# 3-RF_Frontend.net
KiCad netlist of a schematic drawn in Altium Designer
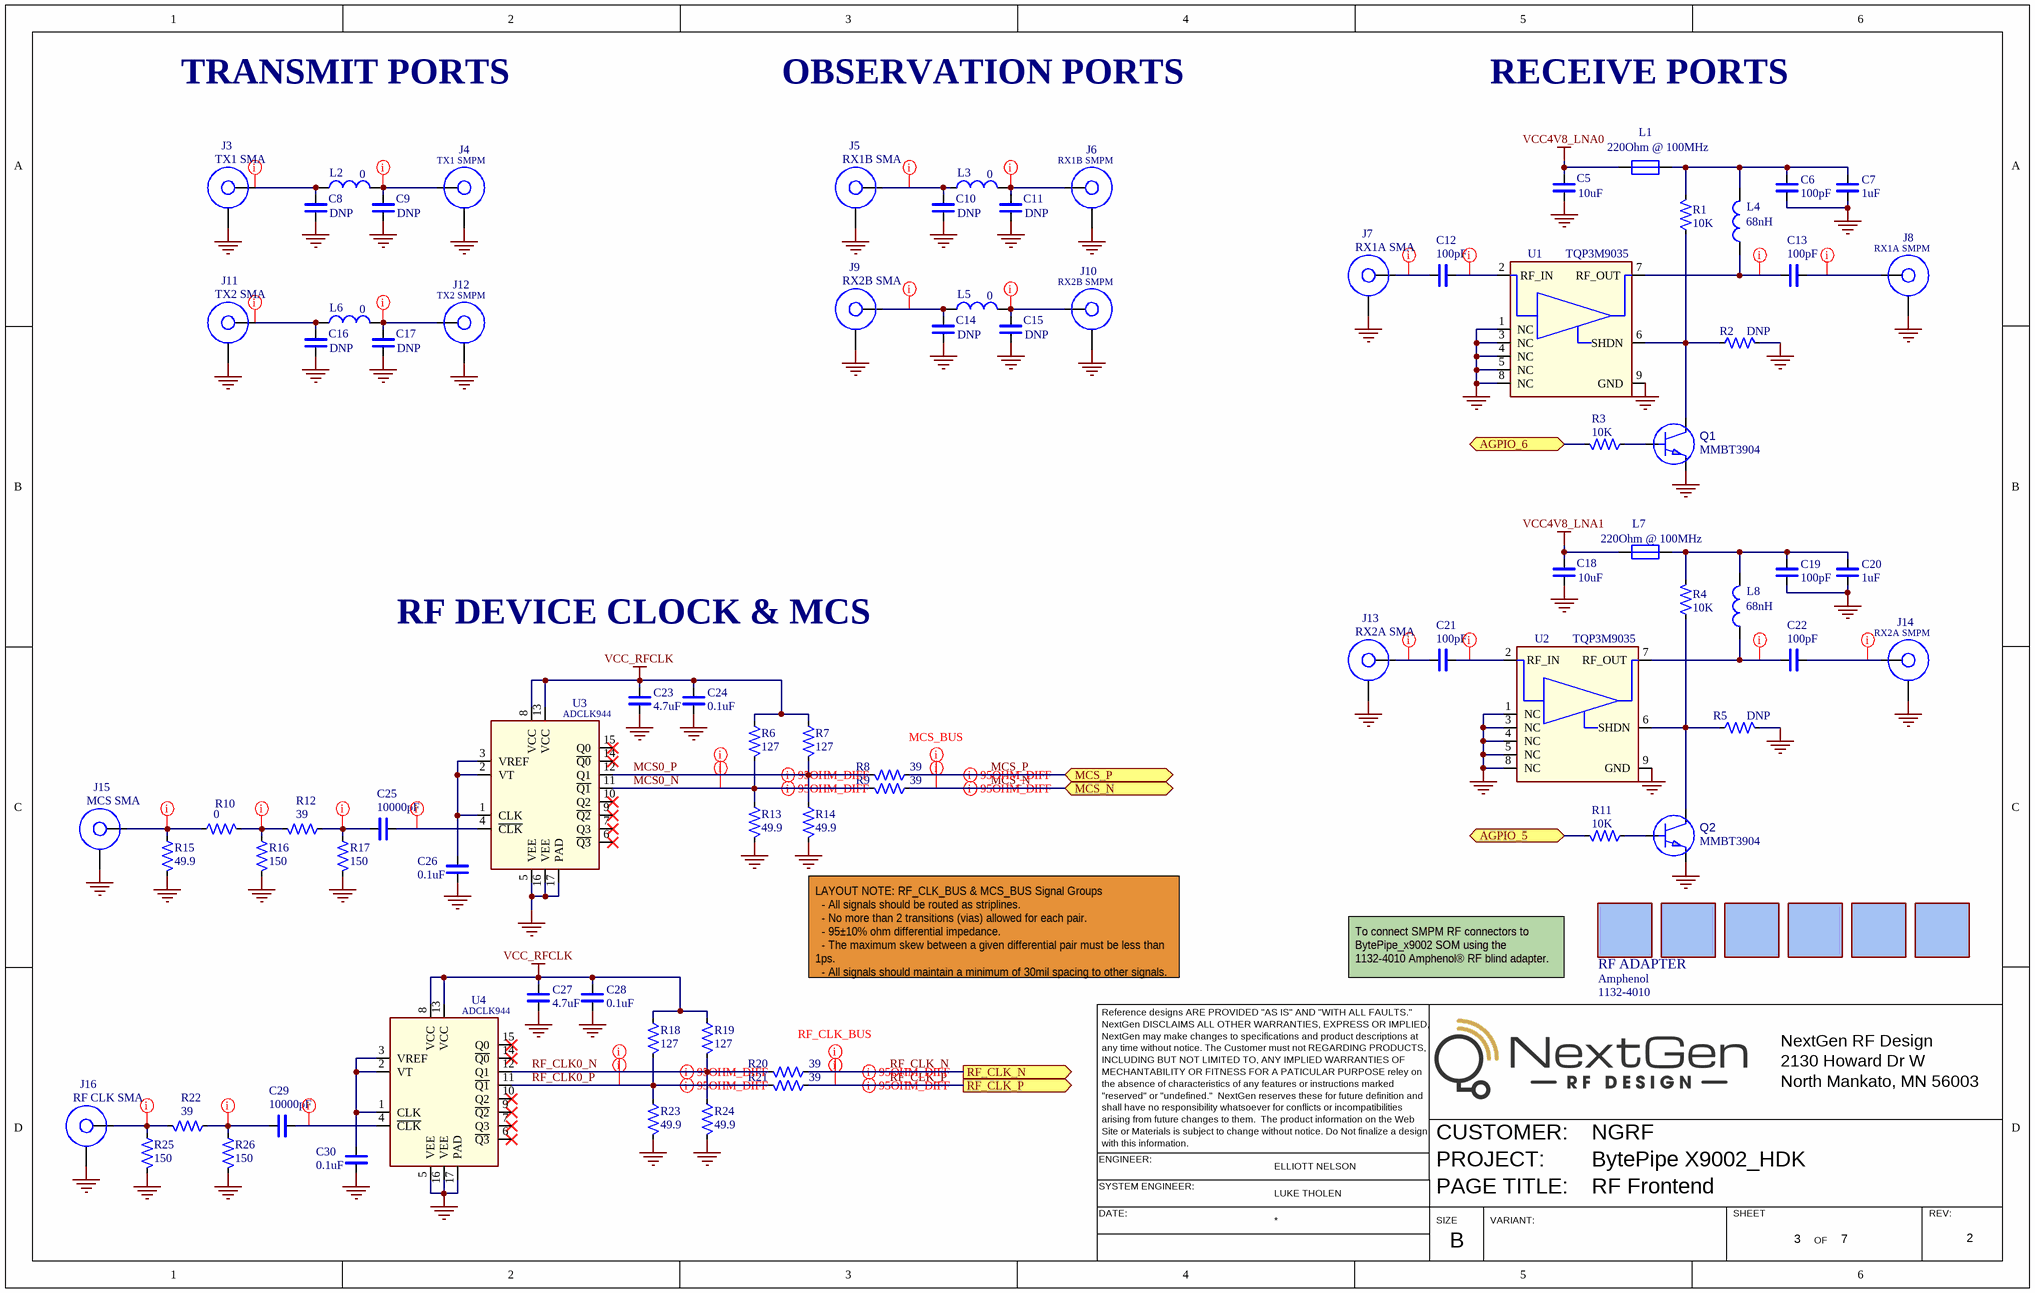
[diagram p0: 3-RF Frontend.SchDoc]

(export (version "E")
  (design (tool "Eeschema 10.0.6"))
  (components
    (comp (ref "B3")
      (value "RF ADAPTER")
      (description "Amphenol® RF SMPM blind adapter")
      (fields (field (name "OEM NAME") "Amphenol") (field (name "OEM#") "1132-4010"))
      (libsource (lib "NextGenRF_Symbols_MECH") (part "BOM_COMPONENT_NO-FOOTPRINT"))
    )
    (comp (ref "B4")
      (value "RF ADAPTER")
      (description "Amphenol® RF SMPM blind adapter")
      (libsource (lib "NextGenRF_Symbols_MECH") (part "BOM_COMPONENT_NO-FOOTPRINT"))
    )
    (comp (ref "B5")
      (value "RF ADAPTER")
      (description "Amphenol® RF SMPM blind adapter")
      (libsource (lib "NextGenRF_Symbols_MECH") (part "BOM_COMPONENT_NO-FOOTPRINT"))
    )
    (comp (ref "B6")
      (value "RF ADAPTER")
      (description "Amphenol® RF SMPM blind adapter")
      (libsource (lib "NextGenRF_Symbols_MECH") (part "BOM_COMPONENT_NO-FOOTPRINT"))
    )
    (comp (ref "B7")
      (value "RF ADAPTER")
      (description "Amphenol® RF SMPM blind adapter")
      (libsource (lib "NextGenRF_Symbols_MECH") (part "BOM_COMPONENT_NO-FOOTPRINT"))
    )
    (comp (ref "B8")
      (value "RF ADAPTER")
      (description "Amphenol® RF SMPM blind adapter")
      (libsource (lib "NextGenRF_Symbols_MECH") (part "BOM_COMPONENT_NO-FOOTPRINT"))
    )
    (comp (ref "C5")
      (value "10uF")
      (footprint "SM/0402/CAP")
      (description "10µF ±20% 10V Ceramic Capacitor X5R 0402 (1005 Metric)")
      (fields (field (name "Comment") "CAP_CERAMIC_0402"))
      (libsource (lib "NextGenRF_Symbols_SMT") (part "CAP_CERAMIC_0402"))
    )
    (comp (ref "C6")
      (value "100pF")
      (footprint "SM/0402/CAP")
      (description "CAP CER 100PF 50V C0G/NP0 0402")
      (fields (field (name "Comment") "CAP_CERAMIC_0402"))
      (libsource (lib "NextGenRF_Symbols_SMT") (part "CAP_CERAMIC_0402"))
    )
    (comp (ref "C7")
      (value "1uF")
      (footprint "SM/0402/CAP")
      (description "CAP CER 1UF 16V X5R 0402")
      (fields (field (name "Comment") "CAP_CERAMIC_0402"))
      (libsource (lib "NextGenRF_Symbols_SMT") (part "CAP_CERAMIC_0402"))
    )
    (comp (ref "C8")
      (value "DNP")
      (footprint "SM/0402/CAP")
      (fields (field (name "Comment") "CAP_CERAMIC_0402"))
      (libsource (lib "NextGenRF_Symbols_SMT") (part "CAP_CERAMIC_0402"))
    )
    (comp (ref "C9")
      (value "DNP")
      (footprint "SM/0402/CAP")
      (fields (field (name "Comment") "CAP_CERAMIC_0402"))
      (libsource (lib "NextGenRF_Symbols_SMT") (part "CAP_CERAMIC_0402"))
    )
    (comp (ref "C10")
      (value "DNP")
      (footprint "SM/0402/CAP")
      (fields (field (name "Comment") "CAP_CERAMIC_0402"))
      (libsource (lib "NextGenRF_Symbols_SMT") (part "CAP_CERAMIC_0402"))
    )
    (comp (ref "C11")
      (value "DNP")
      (footprint "SM/0402/CAP")
      (fields (field (name "Comment") "CAP_CERAMIC_0402"))
      (libsource (lib "NextGenRF_Symbols_SMT") (part "CAP_CERAMIC_0402"))
    )
    (comp (ref "C12")
      (value "100pF")
      (footprint "SM/0402/CAP")
      (description "CAP CER 100PF 50V C0G/NP0 0402")
      (fields (field (name "Comment") "CAP_CERAMIC_0402"))
      (libsource (lib "NextGenRF_Symbols_SMT") (part "CAP_CERAMIC_0402"))
    )
    (comp (ref "C13")
      (value "100pF")
      (footprint "SM/0402/CAP")
      (description "CAP CER 100PF 50V C0G/NP0 0402")
      (fields (field (name "Comment") "CAP_CERAMIC_0402"))
      (libsource (lib "NextGenRF_Symbols_SMT") (part "CAP_CERAMIC_0402"))
    )
    (comp (ref "C14")
      (value "DNP")
      (footprint "SM/0402/CAP")
      (fields (field (name "Comment") "CAP_CERAMIC_0402"))
      (libsource (lib "NextGenRF_Symbols_SMT") (part "CAP_CERAMIC_0402"))
    )
    (comp (ref "C15")
      (value "DNP")
      (footprint "SM/0402/CAP")
      (fields (field (name "Comment") "CAP_CERAMIC_0402"))
      (libsource (lib "NextGenRF_Symbols_SMT") (part "CAP_CERAMIC_0402"))
    )
    (comp (ref "C16")
      (value "DNP")
      (footprint "SM/0402/CAP")
      (fields (field (name "Comment") "CAP_CERAMIC_0402"))
      (libsource (lib "NextGenRF_Symbols_SMT") (part "CAP_CERAMIC_0402"))
    )
    (comp (ref "C17")
      (value "DNP")
      (footprint "SM/0402/CAP")
      (fields (field (name "Comment") "CAP_CERAMIC_0402"))
      (libsource (lib "NextGenRF_Symbols_SMT") (part "CAP_CERAMIC_0402"))
    )
    (comp (ref "C18")
      (value "10uF")
      (footprint "SM/0402/CAP")
      (description "10µF ±20% 10V Ceramic Capacitor X5R 0402 (1005 Metric)")
      (fields (field (name "Comment") "CAP_CERAMIC_0402"))
      (libsource (lib "NextGenRF_Symbols_SMT") (part "CAP_CERAMIC_0402"))
    )
    (comp (ref "C19")
      (value "100pF")
      (footprint "SM/0402/CAP")
      (description "CAP CER 100PF 50V C0G/NP0 0402")
      (fields (field (name "Comment") "CAP_CERAMIC_0402"))
      (libsource (lib "NextGenRF_Symbols_SMT") (part "CAP_CERAMIC_0402"))
    )
    (comp (ref "C20")
      (value "1uF")
      (footprint "SM/0402/CAP")
      (description "CAP CER 1UF 16V X5R 0402")
      (fields (field (name "Comment") "CAP_CERAMIC_0402"))
      (libsource (lib "NextGenRF_Symbols_SMT") (part "CAP_CERAMIC_0402"))
    )
    (comp (ref "C21")
      (value "100pF")
      (footprint "SM/0402/CAP")
      (description "CAP CER 100PF 50V C0G/NP0 0402")
      (fields (field (name "Comment") "CAP_CERAMIC_0402"))
      (libsource (lib "NextGenRF_Symbols_SMT") (part "CAP_CERAMIC_0402"))
    )
    (comp (ref "C22")
      (value "100pF")
      (footprint "SM/0402/CAP")
      (description "CAP CER 100PF 50V C0G/NP0 0402")
      (fields (field (name "Comment") "CAP_CERAMIC_0402"))
      (libsource (lib "NextGenRF_Symbols_SMT") (part "CAP_CERAMIC_0402"))
    )
    (comp (ref "C23")
      (value "4.7uF")
      (footprint "SM/0402/CAP")
      (description "CAP CER 4.7UF 10V X5R 0402")
      (fields (field (name "Comment") "CAP_CERAMIC_0402"))
      (libsource (lib "NextGenRF_Symbols_SMT") (part "CAP_CERAMIC_0402"))
    )
    (comp (ref "C24")
      (value "0.1uF")
      (footprint "SM/0402/CAP")
      (description "CAP CER 0.1UF 25V X7R 0402")
      (fields (field (name "Comment") "CAP_CERAMIC_0402"))
      (libsource (lib "NextGenRF_Symbols_SMT") (part "CAP_CERAMIC_0402"))
    )
    (comp (ref "C25")
      (value "10000pF")
      (footprint "SM/0402/CAP")
      (description "CAP CER 10000PF 50V X7R 0402")
      (fields (field (name "Comment") "CAP_CERAMIC_0402"))
      (libsource (lib "NextGenRF_Symbols_SMT") (part "CAP_CERAMIC_0402"))
    )
    (comp (ref "C26")
      (value "0.1uF")
      (footprint "SM/0402/CAP")
      (description "CAP CER 0.1UF 25V X7R 0402")
      (fields (field (name "Comment") "CAP_CERAMIC_0402"))
      (libsource (lib "NextGenRF_Symbols_SMT") (part "CAP_CERAMIC_0402"))
    )
    (comp (ref "C27")
      (value "4.7uF")
      (footprint "SM/0402/CAP")
      (description "CAP CER 4.7UF 10V X5R 0402")
      (fields (field (name "Comment") "CAP_CERAMIC_0402"))
      (libsource (lib "NextGenRF_Symbols_SMT") (part "CAP_CERAMIC_0402"))
    )
    (comp (ref "C28")
      (value "0.1uF")
      (footprint "SM/0402/CAP")
      (description "CAP CER 0.1UF 25V X7R 0402")
      (fields (field (name "Comment") "CAP_CERAMIC_0402"))
      (libsource (lib "NextGenRF_Symbols_SMT") (part "CAP_CERAMIC_0402"))
    )
    (comp (ref "C29")
      (value "10000pF")
      (footprint "SM/0402/CAP")
      (description "CAP CER 10000PF 50V X7R 0402")
      (fields (field (name "Comment") "CAP_CERAMIC_0402"))
      (libsource (lib "NextGenRF_Symbols_SMT") (part "CAP_CERAMIC_0402"))
    )
    (comp (ref "C30")
      (value "0.1uF")
      (footprint "SM/0402/CAP")
      (description "CAP CER 0.1UF 25V X7R 0402")
      (fields (field (name "Comment") "CAP_CERAMIC_0402"))
      (libsource (lib "NextGenRF_Symbols_SMT") (part "CAP_CERAMIC_0402"))
    )
    (comp (ref "J3")
      (value "TX1 SMA")
      (footprint "NGRF_SMT_Footprints:SM/CON/RF/SMA/BRD-EDGE_C")
      (description "SMA board edge style, .250\" wide style")
      (fields (field (name "Comment") "CON_RF_SMA_BRD-EDGE_C"))
      (libsource (lib "NextGenRF_Symbols_SMT") (part "CON_RF_SMA_BRD-EDGE_C"))
    )
    (comp (ref "J4")
      (value "TX1 SMPM")
      (footprint "SM/CON/RF/SMPM/VERT_A")
      (description "SMPM Connector Plug, Male Pin 50Ohm Surface Mount Solder. Based off of Amphenol 925-144J-51PT")
      (fields (field (name "Comment") "CON_RF_SMPM_SMT_AMPHENOL"))
      (libsource (lib "NextGenRF_Symbols_SMT") (part "CON_RF_SMPM_SMT_AMPHENOL"))
    )
    (comp (ref "J5")
      (value "RX1B SMA")
      (footprint "NGRF_SMT_Footprints:SM/CON/RF/SMA/BRD-EDGE_C")
      (description "SMA board edge style, .250\" wide style")
      (fields (field (name "Comment") "CON_RF_SMA_BRD-EDGE_C"))
      (libsource (lib "NextGenRF_Symbols_SMT") (part "CON_RF_SMA_BRD-EDGE_C"))
    )
    (comp (ref "J6")
      (value "RX1B SMPM")
      (footprint "SM/CON/RF/SMPM/VERT_A")
      (description "SMPM Connector Plug, Male Pin 50Ohm Surface Mount Solder. Based off of Amphenol 925-144J-51PT")
      (fields (field (name "Comment") "CON_RF_SMPM_SMT_AMPHENOL"))
      (libsource (lib "NextGenRF_Symbols_SMT") (part "CON_RF_SMPM_SMT_AMPHENOL"))
    )
    (comp (ref "J7")
      (value "RX1A SMA")
      (footprint "NGRF_SMT_Footprints:SM/CON/RF/SMA/BRD-EDGE_C")
      (description "SMA board edge style, .250\" wide style")
      (fields (field (name "Comment") "CON_RF_SMA_BRD-EDGE_C"))
      (libsource (lib "NextGenRF_Symbols_SMT") (part "CON_RF_SMA_BRD-EDGE_C"))
    )
    (comp (ref "J8")
      (value "RX1A SMPM")
      (footprint "SM/CON/RF/SMPM/VERT_A")
      (description "SMPM Connector Plug, Male Pin 50Ohm Surface Mount Solder. Based off of Amphenol 925-144J-51PT")
      (fields (field (name "Comment") "CON_RF_SMPM_SMT_AMPHENOL"))
      (libsource (lib "NextGenRF_Symbols_SMT") (part "CON_RF_SMPM_SMT_AMPHENOL"))
    )
    (comp (ref "J9")
      (value "RX2B SMA")
      (footprint "NGRF_SMT_Footprints:SM/CON/RF/SMA/BRD-EDGE_C")
      (description "SMA board edge style, .250\" wide style")
      (fields (field (name "Comment") "CON_RF_SMA_BRD-EDGE_C"))
      (libsource (lib "NextGenRF_Symbols_SMT") (part "CON_RF_SMA_BRD-EDGE_C"))
    )
    (comp (ref "J10")
      (value "RX2B SMPM")
      (footprint "SM/CON/RF/SMPM/VERT_A")
      (description "SMPM Connector Plug, Male Pin 50Ohm Surface Mount Solder. Based off of Amphenol 925-144J-51PT")
      (fields (field (name "Comment") "CON_RF_SMPM_SMT_AMPHENOL"))
      (libsource (lib "NextGenRF_Symbols_SMT") (part "CON_RF_SMPM_SMT_AMPHENOL"))
    )
    (comp (ref "J11")
      (value "TX2 SMA")
      (footprint "NGRF_SMT_Footprints:SM/CON/RF/SMA/BRD-EDGE_C")
      (description "SMA board edge style, .250\" wide style")
      (fields (field (name "Comment") "CON_RF_SMA_BRD-EDGE_C"))
      (libsource (lib "NextGenRF_Symbols_SMT") (part "CON_RF_SMA_BRD-EDGE_C"))
    )
    (comp (ref "J12")
      (value "TX2 SMPM")
      (footprint "SM/CON/RF/SMPM/VERT_A")
      (description "SMPM Connector Plug, Male Pin 50Ohm Surface Mount Solder. Based off of Amphenol 925-144J-51PT")
      (fields (field (name "Comment") "CON_RF_SMPM_SMT_AMPHENOL"))
      (libsource (lib "NextGenRF_Symbols_SMT") (part "CON_RF_SMPM_SMT_AMPHENOL"))
    )
    (comp (ref "J13")
      (value "RX2A SMA")
      (footprint "NGRF_SMT_Footprints:SM/CON/RF/SMA/BRD-EDGE_C")
      (description "SMA board edge style, .250\" wide style")
      (fields (field (name "Comment") "CON_RF_SMA_BRD-EDGE_C"))
      (libsource (lib "NextGenRF_Symbols_SMT") (part "CON_RF_SMA_BRD-EDGE_C"))
    )
    (comp (ref "J14")
      (value "RX2A SMPM")
      (footprint "SM/CON/RF/SMPM/VERT_A")
      (description "SMPM Connector Plug, Male Pin 50Ohm Surface Mount Solder. Based off of Amphenol 925-144J-51PT")
      (fields (field (name "Comment") "CON_RF_SMPM_SMT_AMPHENOL"))
      (libsource (lib "NextGenRF_Symbols_SMT") (part "CON_RF_SMPM_SMT_AMPHENOL"))
    )
    (comp (ref "J15")
      (value "MCS SMA")
      (footprint "NGRF_SMT_Footprints:SM/CON/RF/SMA/BRD-EDGE_C")
      (description "SMA board edge style, .250\" wide style")
      (fields (field (name "Comment") "CON_RF_SMA_BRD-EDGE_C"))
      (libsource (lib "NextGenRF_Symbols_SMT") (part "CON_RF_SMA_BRD-EDGE_C"))
    )
    (comp (ref "J16")
      (value "RF CLK SMA")
      (footprint "NGRF_SMT_Footprints:SM/CON/RF/SMA/BRD-EDGE_C")
      (description "SMA board edge style, .250\" wide style")
      (fields (field (name "Comment") "CON_RF_SMA_BRD-EDGE_C"))
      (libsource (lib "NextGenRF_Symbols_SMT") (part "CON_RF_SMA_BRD-EDGE_C"))
    )
    (comp (ref "L1")
      (value "220Ohm @ 100MHz")
      (footprint "NGRF_SMT_Footprints:SM/0603")
      (description "120 Ohms @ 100MHz 1 Power Line Ferrite Bead 0603 (1608 Metric) 3A 25mOhm")
      (fields (field (name "Comment") "FERRITE_0603_A"))
      (libsource (lib "NextGenRF_Symbols_SMT") (part "FERRITE_0603_A"))
    )
    (comp (ref "L2")
      (value "0")
      (footprint "NGRF_SMT_Footprints:SM/0402")
      (description "RES SMD 0 OHM JUMPER 1/10W 0402")
      (fields (field (name "Comment") "IND_0402"))
      (libsource (lib "NextGenRF_Symbols_SMT") (part "IND_0402"))
    )
    (comp (ref "L3")
      (value "0")
      (footprint "NGRF_SMT_Footprints:SM/0402")
      (description "RES SMD 0 OHM JUMPER 1/10W 0402")
      (fields (field (name "Comment") "IND_0402"))
      (libsource (lib "NextGenRF_Symbols_SMT") (part "IND_0402"))
    )
    (comp (ref "L4")
      (value "68nH")
      (footprint "NGRF_SMT_Footprints:SM/0603")
      (description "FIXED IND 68NH 300MA 800 MOHM")
      (fields (field (name "Comment") "IND_0603"))
      (libsource (lib "NextGenRF_Symbols_SMT") (part "IND_0603"))
    )
    (comp (ref "L5")
      (value "0")
      (footprint "NGRF_SMT_Footprints:SM/0402")
      (description "RES SMD 0 OHM JUMPER 1/10W 0402")
      (fields (field (name "Comment") "IND_0402"))
      (libsource (lib "NextGenRF_Symbols_SMT") (part "IND_0402"))
    )
    (comp (ref "L6")
      (value "0")
      (footprint "NGRF_SMT_Footprints:SM/0402")
      (description "RES SMD 0 OHM JUMPER 1/10W 0402")
      (fields (field (name "Comment") "IND_0402"))
      (libsource (lib "NextGenRF_Symbols_SMT") (part "IND_0402"))
    )
    (comp (ref "L7")
      (value "220Ohm @ 100MHz")
      (footprint "NGRF_SMT_Footprints:SM/0603")
      (description "120 Ohms @ 100MHz 1 Power Line Ferrite Bead 0603 (1608 Metric) 3A 25mOhm")
      (fields (field (name "Comment") "FERRITE_0603_A"))
      (libsource (lib "NextGenRF_Symbols_SMT") (part "FERRITE_0603_A"))
    )
    (comp (ref "L8")
      (value "68nH")
      (footprint "NGRF_SMT_Footprints:SM/0603")
      (description "FIXED IND 68NH 300MA 800 MOHM")
      (fields (field (name "Comment") "IND_0603"))
      (libsource (lib "NextGenRF_Symbols_SMT") (part "IND_0603"))
    )
    (comp (ref "Q1")
      (value "MMBT3904")
      (footprint "NGRF_SMT_Footprints:SM/SOT23_A")
      (description "Bipolar (BJT) Transistor NPN 40V 200mA 300MHz 300mW Surface Mount SOT-23-3 (TO-236)")
      (fields (field (name "Comment") "TRANSISTOR_NPN_SOT23"))
      (libsource (lib "NextGenRF_Symbols_SMT") (part "TRANSISTOR_NPN_SOT23"))
    )
    (comp (ref "Q2")
      (value "MMBT3904")
      (footprint "NGRF_SMT_Footprints:SM/SOT23_A")
      (description "Bipolar (BJT) Transistor NPN 40V 200mA 300MHz 300mW Surface Mount SOT-23-3 (TO-236)")
      (fields (field (name "Comment") "TRANSISTOR_NPN_SOT23"))
      (libsource (lib "NextGenRF_Symbols_SMT") (part "TRANSISTOR_NPN_SOT23"))
    )
    (comp (ref "R1")
      (value "10K")
      (footprint "SM/0402/RES")
      (description "RES SMD 10K OHM 1% 1/10W 0402")
      (fields (field (name "Comment") "RES_0402_A"))
      (libsource (lib "NextGenRF_Symbols_SMT") (part "RES_0402_A"))
    )
    (comp (ref "R2")
      (value "DNP")
      (footprint "SM/0402/RES")
      (fields (field (name "Comment") "RES_0402_A"))
      (libsource (lib "NextGenRF_Symbols_SMT") (part "RES_0402_A"))
    )
    (comp (ref "R3")
      (value "10K")
      (footprint "SM/0402/RES")
      (description "RES SMD 10K OHM 1% 1/10W 0402")
      (fields (field (name "Comment") "RES_0402_A"))
      (libsource (lib "NextGenRF_Symbols_SMT") (part "RES_0402_A"))
    )
    (comp (ref "R4")
      (value "10K")
      (footprint "SM/0402/RES")
      (description "RES SMD 10K OHM 1% 1/10W 0402")
      (fields (field (name "Comment") "RES_0402_A"))
      (libsource (lib "NextGenRF_Symbols_SMT") (part "RES_0402_A"))
    )
    (comp (ref "R5")
      (value "DNP")
      (footprint "SM/0402/RES")
      (fields (field (name "Comment") "RES_0402_A"))
      (libsource (lib "NextGenRF_Symbols_SMT") (part "RES_0402_A"))
    )
    (comp (ref "R6")
      (value "127")
      (footprint "SM/0402/RES")
      (description "RES SMD 127 OHM 1% 1/10W 0402")
      (fields (field (name "Comment") "RES_0402_A"))
      (libsource (lib "NextGenRF_Symbols_SMT") (part "RES_0402_A"))
    )
    (comp (ref "R7")
      (value "127")
      (footprint "SM/0402/RES")
      (description "RES SMD 127 OHM 1% 1/10W 0402")
      (fields (field (name "Comment") "RES_0402_A"))
      (libsource (lib "NextGenRF_Symbols_SMT") (part "RES_0402_A"))
    )
    (comp (ref "R8")
      (value "39")
      (footprint "SM/0402/RES")
      (description "RES SMD 39 OHM 1% 1/10W 0402")
      (fields (field (name "Comment") "RES_0402_A"))
      (libsource (lib "NextGenRF_Symbols_SMT") (part "RES_0402_A"))
    )
    (comp (ref "R9")
      (value "39")
      (footprint "SM/0402/RES")
      (description "RES SMD 39 OHM 1% 1/10W 0402")
      (fields (field (name "Comment") "RES_0402_A"))
      (libsource (lib "NextGenRF_Symbols_SMT") (part "RES_0402_A"))
    )
    (comp (ref "R10")
      (value "0")
      (footprint "SM/0402/RES")
      (description "RES SMD 0 OHM JUMPER 1/10W 0402")
      (fields (field (name "Comment") "RES_0402_A"))
      (libsource (lib "NextGenRF_Symbols_SMT") (part "RES_0402_A"))
    )
    (comp (ref "R11")
      (value "10K")
      (footprint "SM/0402/RES")
      (description "RES SMD 10K OHM 1% 1/10W 0402")
      (fields (field (name "Comment") "RES_0402_A"))
      (libsource (lib "NextGenRF_Symbols_SMT") (part "RES_0402_A"))
    )
    (comp (ref "R12")
      (value "39")
      (footprint "SM/0402/RES")
      (description "RES SMD 39 OHM 1% 1/10W 0402")
      (fields (field (name "Comment") "RES_0402_A"))
      (libsource (lib "NextGenRF_Symbols_SMT") (part "RES_0402_A"))
    )
    (comp (ref "R13")
      (value "49.9")
      (footprint "SM/0402/RES")
      (description "RES 49.9 OHM 1% 1/10W 0402")
      (fields (field (name "Comment") "RES_0402_A"))
      (libsource (lib "NextGenRF_Symbols_SMT") (part "RES_0402_A"))
    )
    (comp (ref "R14")
      (value "49.9")
      (footprint "SM/0402/RES")
      (description "RES 49.9 OHM 1% 1/10W 0402")
      (fields (field (name "Comment") "RES_0402_A"))
      (libsource (lib "NextGenRF_Symbols_SMT") (part "RES_0402_A"))
    )
    (comp (ref "R15")
      (value "49.9")
      (footprint "SM/0402/RES")
      (description "RES 49.9 OHM 1% 1/10W 0402")
      (fields (field (name "Comment") "RES_0402_A"))
      (libsource (lib "NextGenRF_Symbols_SMT") (part "RES_0402_A"))
    )
    (comp (ref "R16")
      (value "150")
      (footprint "SM/0402/RES")
      (description "RES SMD 150 OHM 1% 1/10W 0402")
      (fields (field (name "Comment") "RES_0402_A"))
      (libsource (lib "NextGenRF_Symbols_SMT") (part "RES_0402_A"))
    )
    (comp (ref "R17")
      (value "150")
      (footprint "SM/0402/RES")
      (description "RES SMD 150 OHM 1% 1/10W 0402")
      (fields (field (name "Comment") "RES_0402_A"))
      (libsource (lib "NextGenRF_Symbols_SMT") (part "RES_0402_A"))
    )
    (comp (ref "R18")
      (value "127")
      (footprint "SM/0402/RES")
      (description "RES SMD 127 OHM 1% 1/10W 0402")
      (fields (field (name "Comment") "RES_0402_A"))
      (libsource (lib "NextGenRF_Symbols_SMT") (part "RES_0402_A"))
    )
    (comp (ref "R19")
      (value "127")
      (footprint "SM/0402/RES")
      (description "RES SMD 127 OHM 1% 1/10W 0402")
      (fields (field (name "Comment") "RES_0402_A"))
      (libsource (lib "NextGenRF_Symbols_SMT") (part "RES_0402_A"))
    )
    (comp (ref "R20")
      (value "39")
      (footprint "SM/0402/RES")
      (description "RES SMD 39 OHM 1% 1/10W 0402")
      (fields (field (name "Comment") "RES_0402_A"))
      (libsource (lib "NextGenRF_Symbols_SMT") (part "RES_0402_A"))
    )
    (comp (ref "R21")
      (value "39")
      (footprint "SM/0402/RES")
      (description "RES SMD 39 OHM 1% 1/10W 0402")
      (fields (field (name "Comment") "RES_0402_A"))
      (libsource (lib "NextGenRF_Symbols_SMT") (part "RES_0402_A"))
    )
    (comp (ref "R22")
      (value "39")
      (footprint "SM/0402/RES")
      (description "RES SMD 39 OHM 1% 1/10W 0402")
      (fields (field (name "Comment") "RES_0402_A"))
      (libsource (lib "NextGenRF_Symbols_SMT") (part "RES_0402_A"))
    )
    (comp (ref "R23")
      (value "49.9")
      (footprint "SM/0402/RES")
      (description "RES 49.9 OHM 1% 1/10W 0402")
      (fields (field (name "Comment") "RES_0402_A"))
      (libsource (lib "NextGenRF_Symbols_SMT") (part "RES_0402_A"))
    )
    (comp (ref "R24")
      (value "49.9")
      (footprint "SM/0402/RES")
      (description "RES 49.9 OHM 1% 1/10W 0402")
      (fields (field (name "Comment") "RES_0402_A"))
      (libsource (lib "NextGenRF_Symbols_SMT") (part "RES_0402_A"))
    )
    (comp (ref "R25")
      (value "150")
      (footprint "SM/0402/RES")
      (description "RES SMD 150 OHM 1% 1/10W 0402")
      (fields (field (name "Comment") "RES_0402_A"))
      (libsource (lib "NextGenRF_Symbols_SMT") (part "RES_0402_A"))
    )
    (comp (ref "R26")
      (value "150")
      (footprint "SM/0402/RES")
      (description "RES SMD 150 OHM 1% 1/10W 0402")
      (fields (field (name "Comment") "RES_0402_A"))
      (libsource (lib "NextGenRF_Symbols_SMT") (part "RES_0402_A"))
    )
    (comp (ref "U1")
      (value "TQP3M9035")
      (footprint "SM/DFN8/2X2MM_E")
      (description "RF Amplifier 50-4000MHz NF .66dB Gain 16.5dB @1.9GHz")
      (fields (field (name "Comment") "IC_TQP3M9035_DFN-8"))
      (libsource (lib "NextGenRF_Symbols_SMT") (part "IC_TQP3M9035_DFN-8"))
    )
    (comp (ref "U2")
      (value "TQP3M9035")
      (footprint "SM/DFN8/2X2MM_E")
      (description "RF Amplifier 50-4000MHz NF .66dB Gain 16.5dB @1.9GHz")
      (fields (field (name "Comment") "IC_TQP3M9035_DFN-8"))
      (libsource (lib "NextGenRF_Symbols_SMT") (part "IC_TQP3M9035_DFN-8"))
    )
    (comp (ref "U3")
      (value "ADCLK944")
      (footprint "SM/QFN16/3X3/0.5LS_A")
      (description "IC CLK BUFFER 1:4 7GHZ 16LFCSP")
      (fields (field (name "Comment") "IC_ADCLK944_QFN16"))
      (libsource (lib "NextGenRF_Symbols_SMT") (part "IC_ADCLK944_QFN16"))
    )
    (comp (ref "U4")
      (value "ADCLK944")
      (footprint "SM/QFN16/3X3/0.5LS_A")
      (description "IC CLK BUFFER 1:4 7GHZ 16LFCSP")
      (fields (field (name "Comment") "IC_ADCLK944_QFN16"))
      (libsource (lib "NextGenRF_Symbols_SMT") (part "IC_ADCLK944_QFN16"))
    )
  )
  (nets
    (net (code "1") (name "/AGPIO_5") (class "Default")
      (node (ref "R11") (pin "1") (pinfunction "1_1") (pintype "passive"))
    )
    (net (code "2") (name "/AGPIO_6") (class "Default")
      (node (ref "R3") (pin "1") (pinfunction "1_1") (pintype "passive"))
    )
    (net (code "3") (name "/MCS0_N") (class "Default")
      (node (ref "R13") (pin "1") (pinfunction "1_1") (pintype "passive"))
      (node (ref "R6") (pin "2") (pinfunction "2_2") (pintype "passive"))
      (node (ref "R9") (pin "2") (pinfunction "2_2") (pintype "passive"))
      (node (ref "U3") (pin "11") (pinfunction "Q1_11") (pintype "passive"))
    )
    (net (code "4") (name "/MCS0_P") (class "Default")
      (node (ref "R14") (pin "1") (pinfunction "1_1") (pintype "passive"))
      (node (ref "R7") (pin "2") (pinfunction "2_2") (pintype "passive"))
      (node (ref "R8") (pin "2") (pinfunction "2_2") (pintype "passive"))
      (node (ref "U3") (pin "12") (pinfunction "Q1_12") (pintype "passive"))
    )
    (net (code "5") (name "/MCS_N") (class "Default")
      (node (ref "R9") (pin "1") (pinfunction "1_1") (pintype "passive"))
    )
    (net (code "6") (name "/MCS_P") (class "Default")
      (node (ref "R8") (pin "1") (pinfunction "1_1") (pintype "passive"))
    )
    (net (code "7") (name "/RF_CLK0_N") (class "Default")
      (node (ref "R19") (pin "2") (pinfunction "2_2") (pintype "passive"))
      (node (ref "R20") (pin "2") (pinfunction "2_2") (pintype "passive"))
      (node (ref "R24") (pin "1") (pinfunction "1_1") (pintype "passive"))
      (node (ref "U4") (pin "12") (pinfunction "Q1_12") (pintype "passive"))
    )
    (net (code "8") (name "/RF_CLK0_P") (class "Default")
      (node (ref "R18") (pin "2") (pinfunction "2_2") (pintype "passive"))
      (node (ref "R21") (pin "2") (pinfunction "2_2") (pintype "passive"))
      (node (ref "R23") (pin "1") (pinfunction "1_1") (pintype "passive"))
      (node (ref "U4") (pin "11") (pinfunction "Q1_11") (pintype "passive"))
    )
    (net (code "9") (name "/RF_CLK_N") (class "Default")
      (node (ref "R20") (pin "1") (pinfunction "1_1") (pintype "passive"))
    )
    (net (code "10") (name "/RF_CLK_P") (class "Default")
      (node (ref "R21") (pin "1") (pinfunction "1_1") (pintype "passive"))
    )
    (net (code "11") (name "GND") (class "Default")
      (node (ref "C10") (pin "2") (pinfunction "N2_2") (pintype "passive"))
      (node (ref "C11") (pin "2") (pinfunction "N2_2") (pintype "passive"))
      (node (ref "C14") (pin "2") (pinfunction "N2_2") (pintype "passive"))
      (node (ref "C15") (pin "2") (pinfunction "N2_2") (pintype "passive"))
      (node (ref "C16") (pin "2") (pinfunction "N2_2") (pintype "passive"))
      (node (ref "C17") (pin "2") (pinfunction "N2_2") (pintype "passive"))
      (node (ref "C18") (pin "2") (pinfunction "N2_2") (pintype "passive"))
      (node (ref "C19") (pin "2") (pinfunction "N2_2") (pintype "passive"))
      (node (ref "C20") (pin "2") (pinfunction "N2_2") (pintype "passive"))
      (node (ref "C23") (pin "2") (pinfunction "N2_2") (pintype "passive"))
      (node (ref "C24") (pin "2") (pinfunction "N2_2") (pintype "passive"))
      (node (ref "C26") (pin "2") (pinfunction "N2_2") (pintype "passive"))
      (node (ref "C27") (pin "2") (pinfunction "N2_2") (pintype "passive"))
      (node (ref "C28") (pin "2") (pinfunction "N2_2") (pintype "passive"))
      (node (ref "C30") (pin "2") (pinfunction "N2_2") (pintype "passive"))
      (node (ref "C5") (pin "2") (pinfunction "N2_2") (pintype "passive"))
      (node (ref "C6") (pin "2") (pinfunction "N2_2") (pintype "passive"))
      (node (ref "C7") (pin "2") (pinfunction "N2_2") (pintype "passive"))
      (node (ref "C8") (pin "2") (pinfunction "N2_2") (pintype "passive"))
      (node (ref "C9") (pin "2") (pinfunction "N2_2") (pintype "passive"))
      (node (ref "J10") (pin "2") (pinfunction "2_2") (pintype "passive"))
      (node (ref "J11") (pin "2") (pinfunction "2_2") (pintype "passive"))
      (node (ref "J12") (pin "2") (pinfunction "2_2") (pintype "passive"))
      (node (ref "J13") (pin "2") (pinfunction "2_2") (pintype "passive"))
      (node (ref "J14") (pin "2") (pinfunction "2_2") (pintype "passive"))
      (node (ref "J15") (pin "2") (pinfunction "2_2") (pintype "passive"))
      (node (ref "J16") (pin "2") (pinfunction "2_2") (pintype "passive"))
      (node (ref "J3") (pin "2") (pinfunction "2_2") (pintype "passive"))
      (node (ref "J4") (pin "2") (pinfunction "2_2") (pintype "passive"))
      (node (ref "J5") (pin "2") (pinfunction "2_2") (pintype "passive"))
      (node (ref "J6") (pin "2") (pinfunction "2_2") (pintype "passive"))
      (node (ref "J7") (pin "2") (pinfunction "2_2") (pintype "passive"))
      (node (ref "J8") (pin "2") (pinfunction "2_2") (pintype "passive"))
      (node (ref "J9") (pin "2") (pinfunction "2_2") (pintype "passive"))
      (node (ref "Q1") (pin "2") (pinfunction "E_2") (pintype "passive"))
      (node (ref "Q2") (pin "2") (pinfunction "E_2") (pintype "passive"))
      (node (ref "R13") (pin "2") (pinfunction "2_2") (pintype "passive"))
      (node (ref "R14") (pin "2") (pinfunction "2_2") (pintype "passive"))
      (node (ref "R15") (pin "2") (pinfunction "2_2") (pintype "passive"))
      (node (ref "R16") (pin "2") (pinfunction "2_2") (pintype "passive"))
      (node (ref "R17") (pin "2") (pinfunction "2_2") (pintype "passive"))
      (node (ref "R2") (pin "1") (pinfunction "1_1") (pintype "passive"))
      (node (ref "R23") (pin "2") (pinfunction "2_2") (pintype "passive"))
      (node (ref "R24") (pin "2") (pinfunction "2_2") (pintype "passive"))
      (node (ref "R25") (pin "2") (pinfunction "2_2") (pintype "passive"))
      (node (ref "R26") (pin "2") (pinfunction "2_2") (pintype "passive"))
      (node (ref "R5") (pin "1") (pinfunction "1_1") (pintype "passive"))
      (node (ref "U1") (pin "1") (pinfunction "NC_1") (pintype "passive"))
      (node (ref "U1") (pin "3") (pinfunction "NC_3") (pintype "passive"))
      (node (ref "U1") (pin "4") (pinfunction "NC_4") (pintype "passive"))
      (node (ref "U1") (pin "5") (pinfunction "NC_5") (pintype "passive"))
      (node (ref "U1") (pin "8") (pinfunction "NC_8") (pintype "passive"))
      (node (ref "U1") (pin "9") (pinfunction "GND_9") (pintype "passive"))
      (node (ref "U2") (pin "1") (pinfunction "NC_1") (pintype "passive"))
      (node (ref "U2") (pin "3") (pinfunction "NC_3") (pintype "passive"))
      (node (ref "U2") (pin "4") (pinfunction "NC_4") (pintype "passive"))
      (node (ref "U2") (pin "5") (pinfunction "NC_5") (pintype "passive"))
      (node (ref "U2") (pin "8") (pinfunction "NC_8") (pintype "passive"))
      (node (ref "U2") (pin "9") (pinfunction "GND_9") (pintype "passive"))
      (node (ref "U3") (pin "16") (pinfunction "VEE_16") (pintype "passive"))
      (node (ref "U3") (pin "17") (pinfunction "PAD_17") (pintype "passive"))
      (node (ref "U3") (pin "5") (pinfunction "VEE_5") (pintype "passive"))
      (node (ref "U4") (pin "16") (pinfunction "VEE_16") (pintype "passive"))
      (node (ref "U4") (pin "17") (pinfunction "PAD_17") (pintype "passive"))
      (node (ref "U4") (pin "5") (pinfunction "VEE_5") (pintype "passive"))
    )
    (net (code "12") (name "Net-(C6-N1)") (class "Default")
      (node (ref "C6") (pin "1") (pinfunction "N1_1") (pintype "passive"))
      (node (ref "C7") (pin "1") (pinfunction "N1_1") (pintype "passive"))
      (node (ref "L1") (pin "2") (pinfunction "PIN2_2") (pintype "passive"))
      (node (ref "L4") (pin "2") (pinfunction "PIN2_2") (pintype "passive"))
      (node (ref "R1") (pin "1") (pinfunction "1_1") (pintype "passive"))
    )
    (net (code "13") (name "Net-(C8-N1)") (class "Default")
      (node (ref "C8") (pin "1") (pinfunction "N1_1") (pintype "passive"))
      (node (ref "J3") (pin "1") (pinfunction "1_1") (pintype "passive"))
      (node (ref "L2") (pin "1") (pinfunction "PIN1_1") (pintype "passive"))
    )
    (net (code "14") (name "Net-(C9-N1)") (class "Default")
      (node (ref "C9") (pin "1") (pinfunction "N1_1") (pintype "passive"))
      (node (ref "J4") (pin "1") (pinfunction "1_1") (pintype "passive"))
      (node (ref "L2") (pin "2") (pinfunction "PIN2_2") (pintype "passive"))
    )
    (net (code "15") (name "Net-(C10-N1)") (class "Default")
      (node (ref "C10") (pin "1") (pinfunction "N1_1") (pintype "passive"))
      (node (ref "J5") (pin "1") (pinfunction "1_1") (pintype "passive"))
      (node (ref "L3") (pin "1") (pinfunction "PIN1_1") (pintype "passive"))
    )
    (net (code "16") (name "Net-(C11-N1)") (class "Default")
      (node (ref "C11") (pin "1") (pinfunction "N1_1") (pintype "passive"))
      (node (ref "J6") (pin "1") (pinfunction "1_1") (pintype "passive"))
      (node (ref "L3") (pin "2") (pinfunction "PIN2_2") (pintype "passive"))
    )
    (net (code "17") (name "Net-(C12-N1)") (class "Default")
      (node (ref "C12") (pin "1") (pinfunction "N1_1") (pintype "passive"))
      (node (ref "J7") (pin "1") (pinfunction "1_1") (pintype "passive"))
    )
    (net (code "18") (name "Net-(C12-N2)") (class "Default")
      (node (ref "C12") (pin "2") (pinfunction "N2_2") (pintype "passive"))
      (node (ref "U1") (pin "2") (pinfunction "RF_IN_2") (pintype "passive"))
    )
    (net (code "19") (name "Net-(C13-N1)") (class "Default")
      (node (ref "C13") (pin "1") (pinfunction "N1_1") (pintype "passive"))
      (node (ref "L4") (pin "1") (pinfunction "PIN1_1") (pintype "passive"))
      (node (ref "U1") (pin "7") (pinfunction "RF_OUT_7") (pintype "passive"))
    )
    (net (code "20") (name "Net-(C13-N2)") (class "Default")
      (node (ref "C13") (pin "2") (pinfunction "N2_2") (pintype "passive"))
      (node (ref "J8") (pin "1") (pinfunction "1_1") (pintype "passive"))
    )
    (net (code "21") (name "Net-(C14-N1)") (class "Default")
      (node (ref "C14") (pin "1") (pinfunction "N1_1") (pintype "passive"))
      (node (ref "J9") (pin "1") (pinfunction "1_1") (pintype "passive"))
      (node (ref "L5") (pin "1") (pinfunction "PIN1_1") (pintype "passive"))
    )
    (net (code "22") (name "Net-(C15-N1)") (class "Default")
      (node (ref "C15") (pin "1") (pinfunction "N1_1") (pintype "passive"))
      (node (ref "J10") (pin "1") (pinfunction "1_1") (pintype "passive"))
      (node (ref "L5") (pin "2") (pinfunction "PIN2_2") (pintype "passive"))
    )
    (net (code "23") (name "Net-(C16-N1)") (class "Default")
      (node (ref "C16") (pin "1") (pinfunction "N1_1") (pintype "passive"))
      (node (ref "J11") (pin "1") (pinfunction "1_1") (pintype "passive"))
      (node (ref "L6") (pin "1") (pinfunction "PIN1_1") (pintype "passive"))
    )
    (net (code "24") (name "Net-(C17-N1)") (class "Default")
      (node (ref "C17") (pin "1") (pinfunction "N1_1") (pintype "passive"))
      (node (ref "J12") (pin "1") (pinfunction "1_1") (pintype "passive"))
      (node (ref "L6") (pin "2") (pinfunction "PIN2_2") (pintype "passive"))
    )
    (net (code "25") (name "Net-(C19-N1)") (class "Default")
      (node (ref "C19") (pin "1") (pinfunction "N1_1") (pintype "passive"))
      (node (ref "C20") (pin "1") (pinfunction "N1_1") (pintype "passive"))
      (node (ref "L7") (pin "2") (pinfunction "PIN2_2") (pintype "passive"))
      (node (ref "L8") (pin "2") (pinfunction "PIN2_2") (pintype "passive"))
      (node (ref "R4") (pin "1") (pinfunction "1_1") (pintype "passive"))
    )
    (net (code "26") (name "Net-(C21-N1)") (class "Default")
      (node (ref "C21") (pin "1") (pinfunction "N1_1") (pintype "passive"))
      (node (ref "J13") (pin "1") (pinfunction "1_1") (pintype "passive"))
    )
    (net (code "27") (name "Net-(C21-N2)") (class "Default")
      (node (ref "C21") (pin "2") (pinfunction "N2_2") (pintype "passive"))
      (node (ref "U2") (pin "2") (pinfunction "RF_IN_2") (pintype "passive"))
    )
    (net (code "28") (name "Net-(C22-N1)") (class "Default")
      (node (ref "C22") (pin "1") (pinfunction "N1_1") (pintype "passive"))
      (node (ref "L8") (pin "1") (pinfunction "PIN1_1") (pintype "passive"))
      (node (ref "U2") (pin "7") (pinfunction "RF_OUT_7") (pintype "passive"))
    )
    (net (code "29") (name "Net-(C22-N2)") (class "Default")
      (node (ref "C22") (pin "2") (pinfunction "N2_2") (pintype "passive"))
      (node (ref "J14") (pin "1") (pinfunction "1_1") (pintype "passive"))
    )
    (net (code "30") (name "Net-(C25-N1)") (class "Default")
      (node (ref "C25") (pin "1") (pinfunction "N1_1") (pintype "passive"))
      (node (ref "R12") (pin "1") (pinfunction "1_1") (pintype "passive"))
      (node (ref "R17") (pin "1") (pinfunction "1_1") (pintype "passive"))
    )
    (net (code "31") (name "Net-(C25-N2)") (class "Default")
      (node (ref "C25") (pin "2") (pinfunction "N2_2") (pintype "passive"))
      (node (ref "U3") (pin "4") (pinfunction "CLK_4") (pintype "passive"))
    )
    (net (code "32") (name "Net-(C26-N1)") (class "Default")
      (node (ref "C26") (pin "1") (pinfunction "N1_1") (pintype "passive"))
      (node (ref "U3") (pin "1") (pinfunction "CLK_1") (pintype "passive"))
      (node (ref "U3") (pin "2") (pinfunction "VT_2") (pintype "passive"))
      (node (ref "U3") (pin "3") (pinfunction "VREF_3") (pintype "passive"))
    )
    (net (code "33") (name "Net-(C29-N1)") (class "Default")
      (node (ref "C29") (pin "1") (pinfunction "N1_1") (pintype "passive"))
      (node (ref "R22") (pin "1") (pinfunction "1_1") (pintype "passive"))
      (node (ref "R26") (pin "1") (pinfunction "1_1") (pintype "passive"))
    )
    (net (code "34") (name "Net-(C29-N2)") (class "Default")
      (node (ref "C29") (pin "2") (pinfunction "N2_2") (pintype "passive"))
      (node (ref "U4") (pin "4") (pinfunction "CLK_4") (pintype "passive"))
    )
    (net (code "35") (name "Net-(C30-N1)") (class "Default")
      (node (ref "C30") (pin "1") (pinfunction "N1_1") (pintype "passive"))
      (node (ref "U4") (pin "1") (pinfunction "CLK_1") (pintype "passive"))
      (node (ref "U4") (pin "2") (pinfunction "VT_2") (pintype "passive"))
      (node (ref "U4") (pin "3") (pinfunction "VREF_3") (pintype "passive"))
    )
    (net (code "36") (name "Net-(J15-Pad1)") (class "Default")
      (node (ref "J15") (pin "1") (pinfunction "1_1") (pintype "passive"))
      (node (ref "R10") (pin "2") (pinfunction "2_2") (pintype "passive"))
      (node (ref "R15") (pin "1") (pinfunction "1_1") (pintype "passive"))
    )
    (net (code "37") (name "Net-(J16-Pad1)") (class "Default")
      (node (ref "J16") (pin "1") (pinfunction "1_1") (pintype "passive"))
      (node (ref "R22") (pin "2") (pinfunction "2_2") (pintype "passive"))
      (node (ref "R25") (pin "1") (pinfunction "1_1") (pintype "passive"))
    )
    (net (code "38") (name "Net-(Q1-B)") (class "Default")
      (node (ref "Q1") (pin "1") (pinfunction "B_1") (pintype "passive"))
      (node (ref "R3") (pin "2") (pinfunction "2_2") (pintype "passive"))
    )
    (net (code "39") (name "Net-(Q1-C)") (class "Default")
      (node (ref "Q1") (pin "3") (pinfunction "C_3") (pintype "passive"))
      (node (ref "R1") (pin "2") (pinfunction "2_2") (pintype "passive"))
      (node (ref "R2") (pin "2") (pinfunction "2_2") (pintype "passive"))
      (node (ref "U1") (pin "6") (pinfunction "SHDN_6") (pintype "passive"))
    )
    (net (code "40") (name "Net-(Q2-B)") (class "Default")
      (node (ref "Q2") (pin "1") (pinfunction "B_1") (pintype "passive"))
      (node (ref "R11") (pin "2") (pinfunction "2_2") (pintype "passive"))
    )
    (net (code "41") (name "Net-(Q2-C)") (class "Default")
      (node (ref "Q2") (pin "3") (pinfunction "C_3") (pintype "passive"))
      (node (ref "R4") (pin "2") (pinfunction "2_2") (pintype "passive"))
      (node (ref "R5") (pin "2") (pinfunction "2_2") (pintype "passive"))
      (node (ref "U2") (pin "6") (pinfunction "SHDN_6") (pintype "passive"))
    )
    (net (code "42") (name "Net-(R10-Pad1)") (class "Default")
      (node (ref "R10") (pin "1") (pinfunction "1_1") (pintype "passive"))
      (node (ref "R12") (pin "2") (pinfunction "2_2") (pintype "passive"))
      (node (ref "R16") (pin "1") (pinfunction "1_1") (pintype "passive"))
    )
    (net (code "43") (name "VCC4V8_LNA0") (class "Default")
      (node (ref "C5") (pin "1") (pinfunction "N1_1") (pintype "passive"))
      (node (ref "L1") (pin "1") (pinfunction "PIN1_1") (pintype "passive"))
    )
    (net (code "44") (name "VCC4V8_LNA1") (class "Default")
      (node (ref "C18") (pin "1") (pinfunction "N1_1") (pintype "passive"))
      (node (ref "L7") (pin "1") (pinfunction "PIN1_1") (pintype "passive"))
    )
    (net (code "45") (name "VCC_RFCLK") (class "Default")
      (node (ref "C23") (pin "1") (pinfunction "N1_1") (pintype "passive"))
      (node (ref "C24") (pin "1") (pinfunction "N1_1") (pintype "passive"))
      (node (ref "C27") (pin "1") (pinfunction "N1_1") (pintype "passive"))
      (node (ref "C28") (pin "1") (pinfunction "N1_1") (pintype "passive"))
      (node (ref "R18") (pin "1") (pinfunction "1_1") (pintype "passive"))
      (node (ref "R19") (pin "1") (pinfunction "1_1") (pintype "passive"))
      (node (ref "R6") (pin "1") (pinfunction "1_1") (pintype "passive"))
      (node (ref "R7") (pin "1") (pinfunction "1_1") (pintype "passive"))
      (node (ref "U3") (pin "13") (pinfunction "VCC_13") (pintype "passive"))
      (node (ref "U3") (pin "8") (pinfunction "VCC_8") (pintype "passive"))
      (node (ref "U4") (pin "13") (pinfunction "VCC_13") (pintype "passive"))
      (node (ref "U4") (pin "8") (pinfunction "VCC_8") (pintype "passive"))
    )
    (net (code "46") (name "unconnected-(U3-Q0-Pad14)") (class "Default")
      (node (ref "U3") (pin "14") (pinfunction "Q0_14") (pintype "passive+no_connect"))
    )
    (net (code "47") (name "unconnected-(U3-Q0-Pad15)") (class "Default")
      (node (ref "U3") (pin "15") (pinfunction "Q0_15") (pintype "passive+no_connect"))
    )
    (net (code "48") (name "unconnected-(U3-Q2-Pad9)") (class "Default")
      (node (ref "U3") (pin "9") (pinfunction "Q2_9") (pintype "passive+no_connect"))
    )
    (net (code "49") (name "unconnected-(U3-Q2-Pad10)") (class "Default")
      (node (ref "U3") (pin "10") (pinfunction "Q2_10") (pintype "passive+no_connect"))
    )
    (net (code "50") (name "unconnected-(U3-Q3-Pad6)") (class "Default")
      (node (ref "U3") (pin "6") (pinfunction "Q3_6") (pintype "passive+no_connect"))
    )
    (net (code "51") (name "unconnected-(U3-Q3-Pad7)") (class "Default")
      (node (ref "U3") (pin "7") (pinfunction "Q3_7") (pintype "passive+no_connect"))
    )
    (net (code "52") (name "unconnected-(U4-Q0-Pad14)") (class "Default")
      (node (ref "U4") (pin "14") (pinfunction "Q0_14") (pintype "passive+no_connect"))
    )
    (net (code "53") (name "unconnected-(U4-Q0-Pad15)") (class "Default")
      (node (ref "U4") (pin "15") (pinfunction "Q0_15") (pintype "passive+no_connect"))
    )
    (net (code "54") (name "unconnected-(U4-Q2-Pad9)") (class "Default")
      (node (ref "U4") (pin "9") (pinfunction "Q2_9") (pintype "passive+no_connect"))
    )
    (net (code "55") (name "unconnected-(U4-Q2-Pad10)") (class "Default")
      (node (ref "U4") (pin "10") (pinfunction "Q2_10") (pintype "passive+no_connect"))
    )
    (net (code "56") (name "unconnected-(U4-Q3-Pad6)") (class "Default")
      (node (ref "U4") (pin "6") (pinfunction "Q3_6") (pintype "passive+no_connect"))
    )
    (net (code "57") (name "unconnected-(U4-Q3-Pad7)") (class "Default")
      (node (ref "U4") (pin "7") (pinfunction "Q3_7") (pintype "passive+no_connect"))
    )
  )
)
